# ZB2.net
KiCad netlist of a schematic drawn in Altium Designer
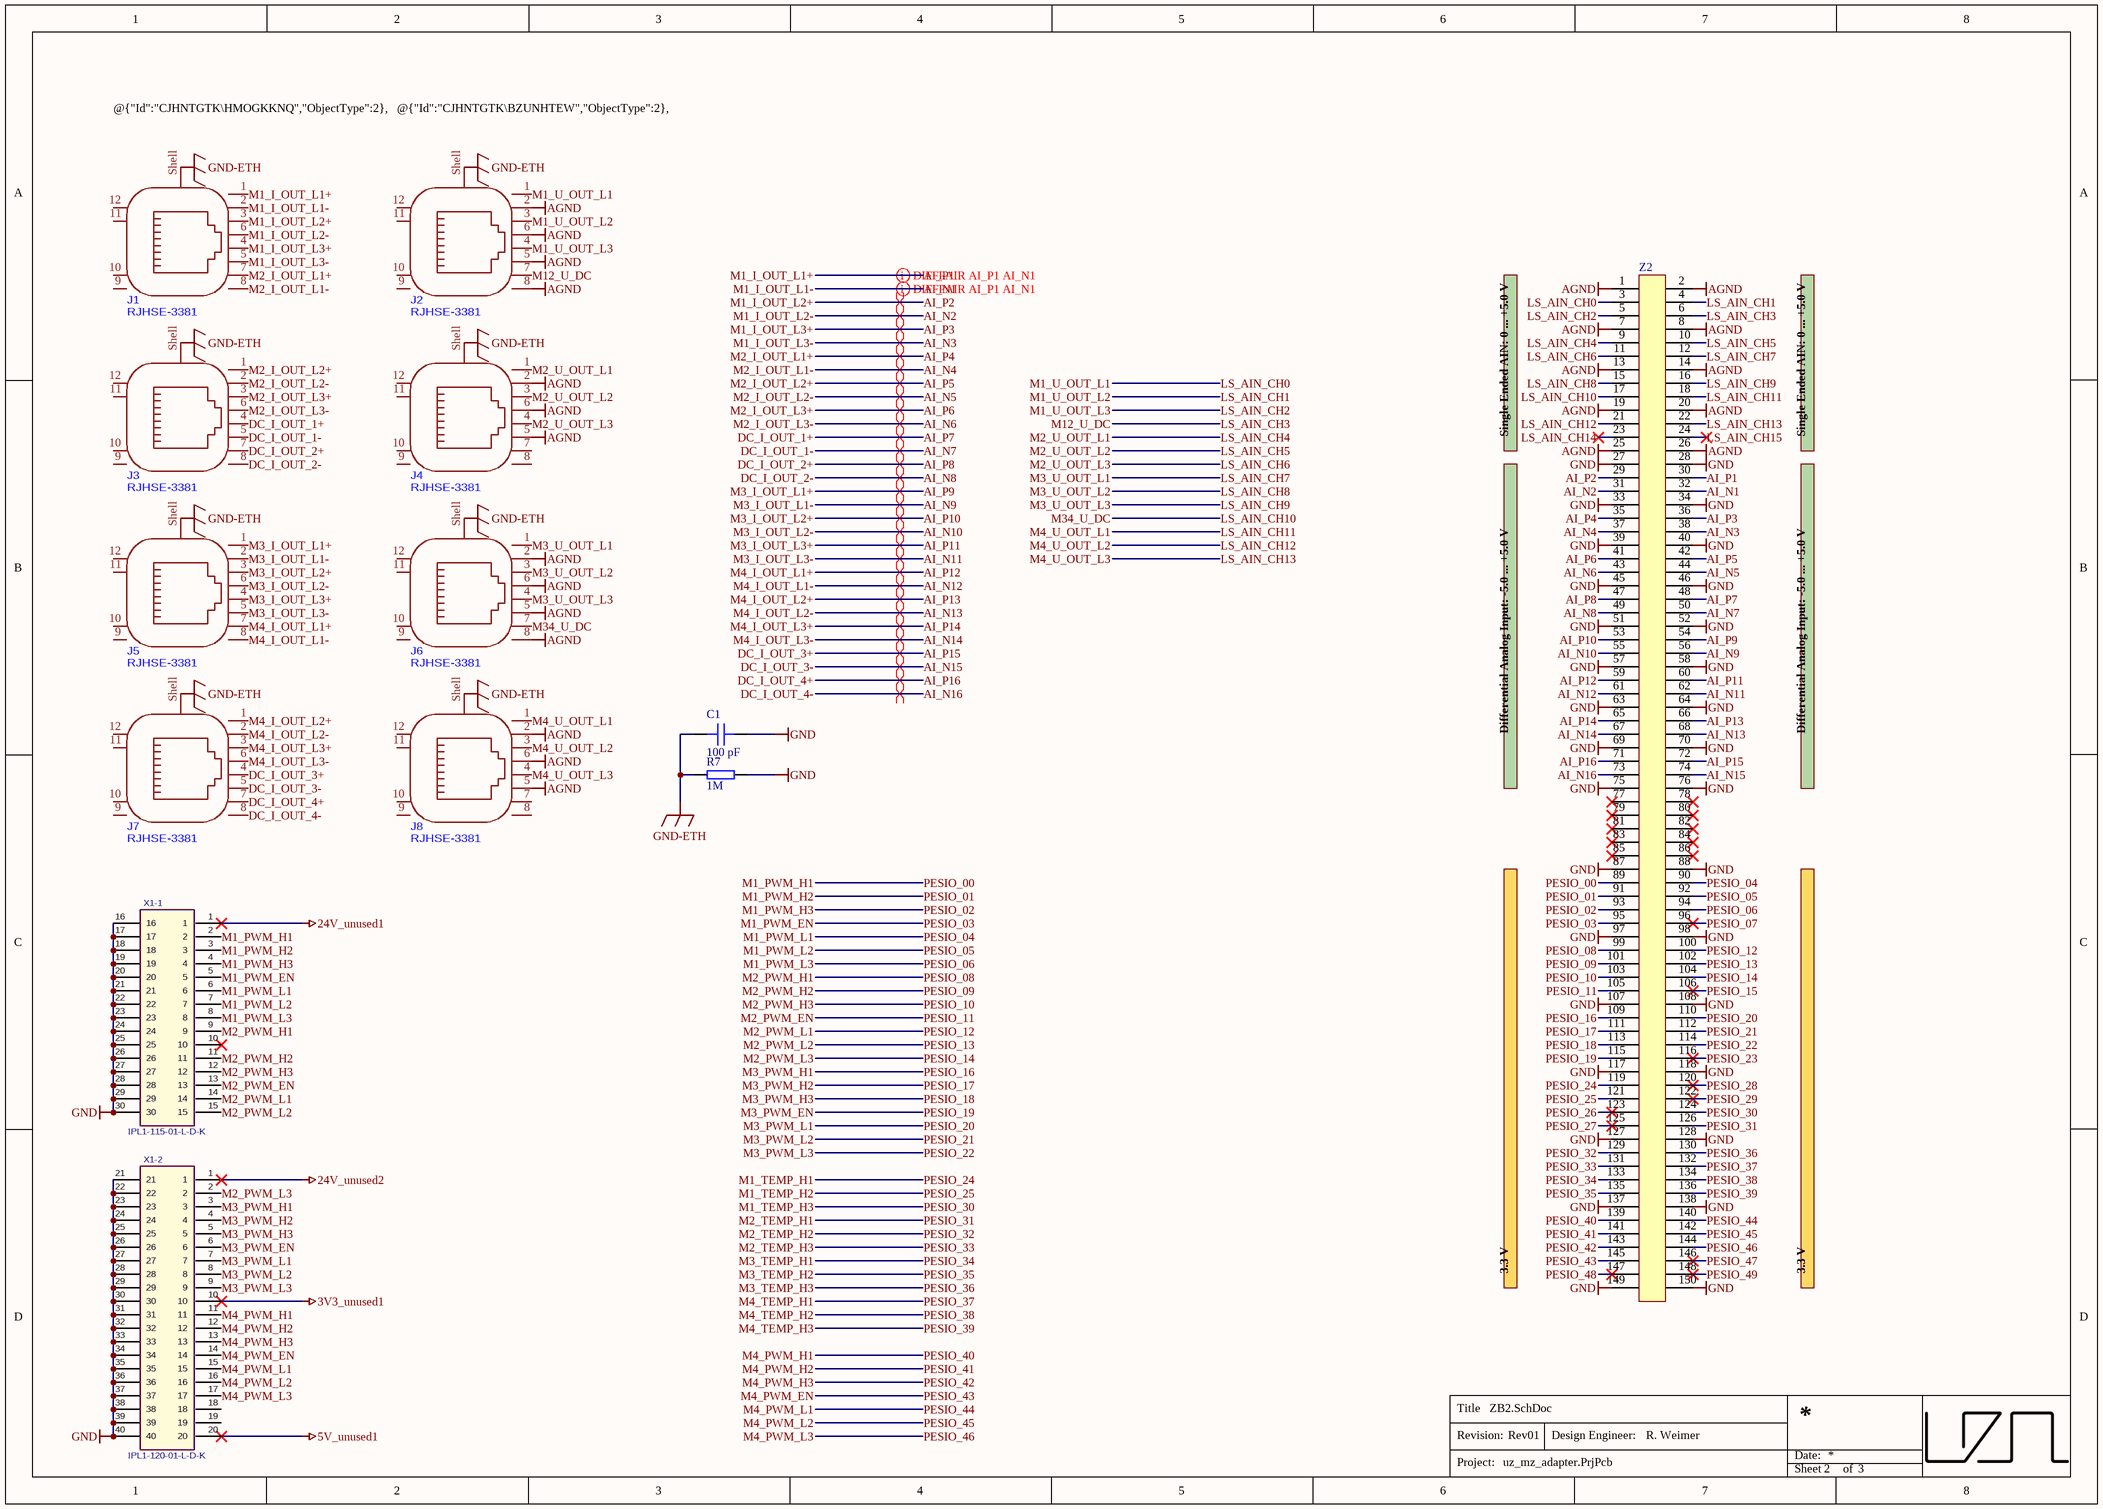
[diagram p0: ZB2.SchDoc]

(export (version "E")
  (design (tool "Eeschema 10.0.6"))
  (components
    (comp (ref "C1")
      (value "100 pF")
      (footprint "C_1206_TE")
      (description "2kV 100pF NP0 ±5% 1206 Multilayer Ceramic Capacitors MLCC - SMD/SMT ROHS")
      (fields
        (field (name "MANUFACTURER PART NUMBER") "CC1206JKNPODBN101")
        (field (name "MANUFACTURER") "YAGEO")
        (field (name "CREATED FROM") "AGeiger")
      )
      (libsource (lib "user") (part "Capacitor"))
    )
    (comp (ref "J1")
      (value "RJHSE-3381")
      (footprint "RJ45-TH_RJHSE-3381")
      (description "CAT5, RJ45 Connector, 1 port, vertical")
      (fields
        (field (name "MANUFACTURER") "Amphenol")
        (field (name "LCSC PART NUMBER") "C599439")
        (field (name "CREATED FROM") "RWeimer")
      )
      (libsource (lib "user") (part "RJHSE-3381"))
    )
    (comp (ref "J2")
      (value "RJHSE-3381")
      (footprint "RJ45-TH_RJHSE-3381")
      (description "CAT5, RJ45 Connector, 1 port, vertical")
      (fields
        (field (name "MANUFACTURER") "Amphenol")
        (field (name "LCSC PART NUMBER") "C599439")
        (field (name "CREATED FROM") "RWeimer")
      )
      (libsource (lib "user") (part "RJHSE-3381"))
    )
    (comp (ref "J3")
      (value "RJHSE-3381")
      (footprint "RJ45-TH_RJHSE-3381")
      (description "CAT5, RJ45 Connector, 1 port, vertical")
      (fields
        (field (name "MANUFACTURER") "Amphenol")
        (field (name "LCSC PART NUMBER") "C599439")
        (field (name "CREATED FROM") "RWeimer")
      )
      (libsource (lib "user") (part "RJHSE-3381"))
    )
    (comp (ref "J4")
      (value "RJHSE-3381")
      (footprint "RJ45-TH_RJHSE-3381")
      (description "CAT5, RJ45 Connector, 1 port, vertical")
      (fields
        (field (name "MANUFACTURER") "Amphenol")
        (field (name "LCSC PART NUMBER") "C599439")
        (field (name "CREATED FROM") "RWeimer")
      )
      (libsource (lib "user") (part "RJHSE-3381"))
    )
    (comp (ref "J5")
      (value "RJHSE-3381")
      (footprint "RJ45-TH_RJHSE-3381")
      (description "CAT5, RJ45 Connector, 1 port, vertical")
      (fields
        (field (name "MANUFACTURER") "Amphenol")
        (field (name "LCSC PART NUMBER") "C599439")
        (field (name "CREATED FROM") "RWeimer")
      )
      (libsource (lib "user") (part "RJHSE-3381"))
    )
    (comp (ref "J6")
      (value "RJHSE-3381")
      (footprint "RJ45-TH_RJHSE-3381")
      (description "CAT5, RJ45 Connector, 1 port, vertical")
      (fields
        (field (name "MANUFACTURER") "Amphenol")
        (field (name "LCSC PART NUMBER") "C599439")
        (field (name "CREATED FROM") "RWeimer")
      )
      (libsource (lib "user") (part "RJHSE-3381"))
    )
    (comp (ref "J7")
      (value "RJHSE-3381")
      (footprint "RJ45-TH_RJHSE-3381")
      (description "CAT5, RJ45 Connector, 1 port, vertical")
      (fields
        (field (name "MANUFACTURER") "Amphenol")
        (field (name "LCSC PART NUMBER") "C599439")
        (field (name "CREATED FROM") "RWeimer")
      )
      (libsource (lib "user") (part "RJHSE-3381"))
    )
    (comp (ref "J8")
      (value "RJHSE-3381")
      (footprint "RJ45-TH_RJHSE-3381")
      (description "CAT5, RJ45 Connector, 1 port, vertical")
      (fields
        (field (name "MANUFACTURER") "Amphenol")
        (field (name "LCSC PART NUMBER") "C599439")
        (field (name "CREATED FROM") "RWeimer")
      )
      (libsource (lib "user") (part "RJHSE-3381"))
    )
    (comp (ref "R7")
      (value "1M")
      (footprint "RES 1206_3216")
      (fields
        (field (name "MANUFACTURER PART NUMBER") "1206W4F1004T5E")
        (field (name "MANUFACTURER") "UNI-ROYAL")
        (field (name "TOLERANCE") "1%")
        (field (name "CREATED FROM") "AGeiger")
      )
      (libsource (lib "user") (part "Resistor"))
    )
    (comp (ref "X1-1")
      (value "IPL1-115-01-L-D-K")
      (footprint "IPL1-115-01-YYY-D-K")
      (description "2.54 mm Double Row Terminal Assembly")
      (fields
        (field (name "MANUFACTURER") "SAMTEC")
        (field (name "LCSC PART NUMBER") "C17431809")
        (field (name "CREATED FROM") "MGremer")
      )
      (libsource (lib "user") (part "IPL1-115-01-XX-D-XX"))
    )
    (comp (ref "X1-2")
      (value "IPL1-120-01-L-D-K")
      (footprint "SAMTEC_IPL1-120-01-X-D-K")
      (description "Terminal Assembly, Double Row, Thru-Hole, 2.54 mm x 2.54 mm Pitch, 40 Pins")
      (fields
        (field (name "MANUFACTURER") "SAMTEC")
        (field (name "LCSC PART NUMBER") "C17429670")
        (field (name "CREATED FROM") "PBaumann")
      )
      (libsource (lib "user") (part "IPL1-120-01-XX-D-XX"))
    )
    (comp (ref "Z2")
      (value "~")
      (footprint "ERM8-075-02.0-L-DV")
      (description "0.80 mm Edge Rate Rugged High Speed")
      (fields
        (field (name "MANUFACTURER PART NUMBER") "ERM8-075-02.0-L-DV-TR")
        (field (name "MANUFACTURER") "SAMTEC")
        (field (name "CREATED FROM") "AGeiger")
      )
      (libsource (lib "user") (part "CON-150"))
    )
  )
  (nets
    (net (code "1") (name "/AI_N1") (class "Default")
      (node (ref "J1") (pin "2") (pinfunction "2_2") (pintype "passive"))
      (node (ref "Z2") (pin "32") (pinfunction "32_32") (pintype "passive"))
    )
    (net (code "2") (name "/AI_N2") (class "Default")
      (node (ref "J1") (pin "6") (pinfunction "6_6") (pintype "passive"))
      (node (ref "Z2") (pin "31") (pinfunction "31_31") (pintype "passive"))
    )
    (net (code "3") (name "/AI_N3") (class "Default")
      (node (ref "J1") (pin "5") (pinfunction "5_5") (pintype "passive"))
      (node (ref "Z2") (pin "38") (pinfunction "38_38") (pintype "passive"))
    )
    (net (code "4") (name "/AI_N4") (class "Default")
      (node (ref "J1") (pin "8") (pinfunction "8_8") (pintype "passive"))
      (node (ref "Z2") (pin "37") (pinfunction "37_37") (pintype "passive"))
    )
    (net (code "5") (name "/AI_N5") (class "Default")
      (node (ref "J3") (pin "2") (pinfunction "2_2") (pintype "passive"))
      (node (ref "Z2") (pin "44") (pinfunction "44_44") (pintype "passive"))
    )
    (net (code "6") (name "/AI_N6") (class "Default")
      (node (ref "J3") (pin "6") (pinfunction "6_6") (pintype "passive"))
      (node (ref "Z2") (pin "43") (pinfunction "43_43") (pintype "passive"))
    )
    (net (code "7") (name "/AI_N7") (class "Default")
      (node (ref "J3") (pin "5") (pinfunction "5_5") (pintype "passive"))
      (node (ref "Z2") (pin "50") (pinfunction "50_50") (pintype "passive"))
    )
    (net (code "8") (name "/AI_N8") (class "Default")
      (node (ref "J3") (pin "8") (pinfunction "8_8") (pintype "passive"))
      (node (ref "Z2") (pin "49") (pinfunction "49_49") (pintype "passive"))
    )
    (net (code "9") (name "/AI_N9") (class "Default")
      (node (ref "J5") (pin "2") (pinfunction "2_2") (pintype "passive"))
      (node (ref "Z2") (pin "56") (pinfunction "56_56") (pintype "passive"))
    )
    (net (code "10") (name "/AI_N10") (class "Default")
      (node (ref "J5") (pin "6") (pinfunction "6_6") (pintype "passive"))
      (node (ref "Z2") (pin "55") (pinfunction "55_55") (pintype "passive"))
    )
    (net (code "11") (name "/AI_N11") (class "Default")
      (node (ref "J5") (pin "5") (pinfunction "5_5") (pintype "passive"))
      (node (ref "Z2") (pin "62") (pinfunction "62_62") (pintype "passive"))
    )
    (net (code "12") (name "/AI_N12") (class "Default")
      (node (ref "J5") (pin "8") (pinfunction "8_8") (pintype "passive"))
      (node (ref "Z2") (pin "61") (pinfunction "61_61") (pintype "passive"))
    )
    (net (code "13") (name "/AI_N13") (class "Default")
      (node (ref "J7") (pin "2") (pinfunction "2_2") (pintype "passive"))
      (node (ref "Z2") (pin "68") (pinfunction "68_68") (pintype "passive"))
    )
    (net (code "14") (name "/AI_N14") (class "Default")
      (node (ref "J7") (pin "6") (pinfunction "6_6") (pintype "passive"))
      (node (ref "Z2") (pin "67") (pinfunction "67_67") (pintype "passive"))
    )
    (net (code "15") (name "/AI_N15") (class "Default")
      (node (ref "J7") (pin "5") (pinfunction "5_5") (pintype "passive"))
      (node (ref "Z2") (pin "74") (pinfunction "74_74") (pintype "passive"))
    )
    (net (code "16") (name "/AI_N16") (class "Default")
      (node (ref "J7") (pin "8") (pinfunction "8_8") (pintype "passive"))
      (node (ref "Z2") (pin "73") (pinfunction "73_73") (pintype "passive"))
    )
    (net (code "17") (name "/AI_P1") (class "Default")
      (node (ref "J1") (pin "1") (pinfunction "1_1") (pintype "passive"))
      (node (ref "Z2") (pin "30") (pinfunction "30_30") (pintype "passive"))
    )
    (net (code "18") (name "/AI_P2") (class "Default")
      (node (ref "J1") (pin "3") (pinfunction "3_3") (pintype "passive"))
      (node (ref "Z2") (pin "29") (pinfunction "29_29") (pintype "passive"))
    )
    (net (code "19") (name "/AI_P3") (class "Default")
      (node (ref "J1") (pin "4") (pinfunction "5_4") (pintype "passive"))
      (node (ref "Z2") (pin "36") (pinfunction "36_36") (pintype "passive"))
    )
    (net (code "20") (name "/AI_P4") (class "Default")
      (node (ref "J1") (pin "7") (pinfunction "7_7") (pintype "passive"))
      (node (ref "Z2") (pin "35") (pinfunction "35_35") (pintype "passive"))
    )
    (net (code "21") (name "/AI_P5") (class "Default")
      (node (ref "J3") (pin "1") (pinfunction "1_1") (pintype "passive"))
      (node (ref "Z2") (pin "42") (pinfunction "42_42") (pintype "passive"))
    )
    (net (code "22") (name "/AI_P6") (class "Default")
      (node (ref "J3") (pin "3") (pinfunction "3_3") (pintype "passive"))
      (node (ref "Z2") (pin "41") (pinfunction "41_41") (pintype "passive"))
    )
    (net (code "23") (name "/AI_P7") (class "Default")
      (node (ref "J3") (pin "4") (pinfunction "5_4") (pintype "passive"))
      (node (ref "Z2") (pin "48") (pinfunction "48_48") (pintype "passive"))
    )
    (net (code "24") (name "/AI_P8") (class "Default")
      (node (ref "J3") (pin "7") (pinfunction "7_7") (pintype "passive"))
      (node (ref "Z2") (pin "47") (pinfunction "47_47") (pintype "passive"))
    )
    (net (code "25") (name "/AI_P9") (class "Default")
      (node (ref "J5") (pin "1") (pinfunction "1_1") (pintype "passive"))
      (node (ref "Z2") (pin "54") (pinfunction "54_54") (pintype "passive"))
    )
    (net (code "26") (name "/AI_P10") (class "Default")
      (node (ref "J5") (pin "3") (pinfunction "3_3") (pintype "passive"))
      (node (ref "Z2") (pin "53") (pinfunction "53_53") (pintype "passive"))
    )
    (net (code "27") (name "/AI_P11") (class "Default")
      (node (ref "J5") (pin "4") (pinfunction "5_4") (pintype "passive"))
      (node (ref "Z2") (pin "60") (pinfunction "60_60") (pintype "passive"))
    )
    (net (code "28") (name "/AI_P12") (class "Default")
      (node (ref "J5") (pin "7") (pinfunction "7_7") (pintype "passive"))
      (node (ref "Z2") (pin "59") (pinfunction "59_59") (pintype "passive"))
    )
    (net (code "29") (name "/AI_P13") (class "Default")
      (node (ref "J7") (pin "1") (pinfunction "1_1") (pintype "passive"))
      (node (ref "Z2") (pin "66") (pinfunction "66_66") (pintype "passive"))
    )
    (net (code "30") (name "/AI_P14") (class "Default")
      (node (ref "J7") (pin "3") (pinfunction "3_3") (pintype "passive"))
      (node (ref "Z2") (pin "65") (pinfunction "65_65") (pintype "passive"))
    )
    (net (code "31") (name "/AI_P15") (class "Default")
      (node (ref "J7") (pin "4") (pinfunction "5_4") (pintype "passive"))
      (node (ref "Z2") (pin "72") (pinfunction "72_72") (pintype "passive"))
    )
    (net (code "32") (name "/AI_P16") (class "Default")
      (node (ref "J7") (pin "7") (pinfunction "7_7") (pintype "passive"))
      (node (ref "Z2") (pin "71") (pinfunction "71_71") (pintype "passive"))
    )
    (net (code "33") (name "/LS_AIN_CH0") (class "Default")
      (node (ref "J2") (pin "1") (pinfunction "1_1") (pintype "passive"))
      (node (ref "Z2") (pin "3") (pinfunction "3_3") (pintype "passive"))
    )
    (net (code "34") (name "/LS_AIN_CH1") (class "Default")
      (node (ref "J2") (pin "3") (pinfunction "3_3") (pintype "passive"))
      (node (ref "Z2") (pin "4") (pinfunction "4_4") (pintype "passive"))
    )
    (net (code "35") (name "/LS_AIN_CH2") (class "Default")
      (node (ref "J2") (pin "4") (pinfunction "5_4") (pintype "passive"))
      (node (ref "Z2") (pin "5") (pinfunction "5_5") (pintype "passive"))
    )
    (net (code "36") (name "/LS_AIN_CH3") (class "Default")
      (node (ref "J2") (pin "7") (pinfunction "7_7") (pintype "passive"))
      (node (ref "Z2") (pin "6") (pinfunction "6_6") (pintype "passive"))
    )
    (net (code "37") (name "/LS_AIN_CH4") (class "Default")
      (node (ref "J4") (pin "1") (pinfunction "1_1") (pintype "passive"))
      (node (ref "Z2") (pin "9") (pinfunction "9_9") (pintype "passive"))
    )
    (net (code "38") (name "/LS_AIN_CH5") (class "Default")
      (node (ref "J4") (pin "3") (pinfunction "3_3") (pintype "passive"))
      (node (ref "Z2") (pin "10") (pinfunction "10_10") (pintype "passive"))
    )
    (net (code "39") (name "/LS_AIN_CH6") (class "Default")
      (node (ref "J4") (pin "4") (pinfunction "5_4") (pintype "passive"))
      (node (ref "Z2") (pin "11") (pinfunction "11_11") (pintype "passive"))
    )
    (net (code "40") (name "/LS_AIN_CH7") (class "Default")
      (node (ref "J6") (pin "1") (pinfunction "1_1") (pintype "passive"))
      (node (ref "Z2") (pin "12") (pinfunction "12_12") (pintype "passive"))
    )
    (net (code "41") (name "/LS_AIN_CH8") (class "Default")
      (node (ref "J6") (pin "3") (pinfunction "3_3") (pintype "passive"))
      (node (ref "Z2") (pin "15") (pinfunction "15_15") (pintype "passive"))
    )
    (net (code "42") (name "/LS_AIN_CH9") (class "Default")
      (node (ref "J6") (pin "4") (pinfunction "5_4") (pintype "passive"))
      (node (ref "Z2") (pin "16") (pinfunction "16_16") (pintype "passive"))
    )
    (net (code "43") (name "/LS_AIN_CH10") (class "Default")
      (node (ref "J6") (pin "7") (pinfunction "7_7") (pintype "passive"))
      (node (ref "Z2") (pin "17") (pinfunction "17_17") (pintype "passive"))
    )
    (net (code "44") (name "/LS_AIN_CH11") (class "Default")
      (node (ref "J8") (pin "1") (pinfunction "1_1") (pintype "passive"))
      (node (ref "Z2") (pin "18") (pinfunction "18_18") (pintype "passive"))
    )
    (net (code "45") (name "/LS_AIN_CH12") (class "Default")
      (node (ref "J8") (pin "3") (pinfunction "3_3") (pintype "passive"))
      (node (ref "Z2") (pin "21") (pinfunction "21_21") (pintype "passive"))
    )
    (net (code "46") (name "/LS_AIN_CH13") (class "Default")
      (node (ref "J8") (pin "4") (pinfunction "5_4") (pintype "passive"))
      (node (ref "Z2") (pin "22") (pinfunction "22_22") (pintype "passive"))
    )
    (net (code "47") (name "/LS_AIN_CH14") (class "Default")
      (node (ref "Z2") (pin "23") (pinfunction "23_23") (pintype "passive+no_connect"))
    )
    (net (code "48") (name "/LS_AIN_CH15") (class "Default")
      (node (ref "Z2") (pin "24") (pinfunction "24_24") (pintype "passive+no_connect"))
    )
    (net (code "49") (name "/M1_PWM_EN") (class "Default")
      (node (ref "X1-1") (pin "5") (pinfunction "5_5") (pintype "passive"))
      (node (ref "Z2") (pin "95") (pinfunction "95_95") (pintype "passive"))
    )
    (net (code "50") (name "/M1_PWM_H1") (class "Default")
      (node (ref "X1-1") (pin "2") (pinfunction "2_2") (pintype "passive"))
      (node (ref "Z2") (pin "89") (pinfunction "89_89") (pintype "passive"))
    )
    (net (code "51") (name "/M1_PWM_H2") (class "Default")
      (node (ref "X1-1") (pin "3") (pinfunction "3_3") (pintype "passive"))
      (node (ref "Z2") (pin "91") (pinfunction "91_91") (pintype "passive"))
    )
    (net (code "52") (name "/M1_PWM_H3") (class "Default")
      (node (ref "X1-1") (pin "4") (pinfunction "4_4") (pintype "passive"))
      (node (ref "Z2") (pin "93") (pinfunction "93_93") (pintype "passive"))
    )
    (net (code "53") (name "/M1_PWM_L1") (class "Default")
      (node (ref "X1-1") (pin "6") (pinfunction "6_6") (pintype "passive"))
      (node (ref "Z2") (pin "90") (pinfunction "90_90") (pintype "passive"))
    )
    (net (code "54") (name "/M1_PWM_L2") (class "Default")
      (node (ref "X1-1") (pin "7") (pinfunction "7_7") (pintype "passive"))
      (node (ref "Z2") (pin "92") (pinfunction "92_92") (pintype "passive"))
    )
    (net (code "55") (name "/M1_PWM_L3") (class "Default")
      (node (ref "X1-1") (pin "8") (pinfunction "8_8") (pintype "passive"))
      (node (ref "Z2") (pin "94") (pinfunction "94_94") (pintype "passive"))
    )
    (net (code "56") (name "/M1_TEMP_H1") (class "Default")
      (node (ref "Z2") (pin "119") (pinfunction "119_119") (pintype "passive"))
    )
    (net (code "57") (name "/M1_TEMP_H2") (class "Default")
      (node (ref "Z2") (pin "121") (pinfunction "121_121") (pintype "passive"))
    )
    (net (code "58") (name "/M1_TEMP_H3") (class "Default")
      (node (ref "Z2") (pin "124") (pinfunction "124_124") (pintype "passive"))
    )
    (net (code "59") (name "/M2_PWM_EN") (class "Default")
      (node (ref "X1-1") (pin "13") (pinfunction "13_13") (pintype "passive"))
      (node (ref "Z2") (pin "105") (pinfunction "105_105") (pintype "passive"))
    )
    (net (code "60") (name "/M2_PWM_H1") (class "Default")
      (node (ref "X1-1") (pin "9") (pinfunction "9_9") (pintype "passive"))
      (node (ref "Z2") (pin "99") (pinfunction "99_99") (pintype "passive"))
    )
    (net (code "61") (name "/M2_PWM_H2") (class "Default")
      (node (ref "X1-1") (pin "11") (pinfunction "11_11") (pintype "passive"))
      (node (ref "Z2") (pin "101") (pinfunction "101_101") (pintype "passive"))
    )
    (net (code "62") (name "/M2_PWM_H3") (class "Default")
      (node (ref "X1-1") (pin "12") (pinfunction "12_12") (pintype "passive"))
      (node (ref "Z2") (pin "103") (pinfunction "103_103") (pintype "passive"))
    )
    (net (code "63") (name "/M2_PWM_L1") (class "Default")
      (node (ref "X1-1") (pin "14") (pinfunction "14_14") (pintype "passive"))
      (node (ref "Z2") (pin "100") (pinfunction "100_100") (pintype "passive"))
    )
    (net (code "64") (name "/M2_PWM_L2") (class "Default")
      (node (ref "X1-1") (pin "15") (pinfunction "15_15") (pintype "passive"))
      (node (ref "Z2") (pin "102") (pinfunction "102_102") (pintype "passive"))
    )
    (net (code "65") (name "/M2_PWM_L3") (class "Default")
      (node (ref "X1-2") (pin "2") (pinfunction "2_2") (pintype "passive"))
      (node (ref "Z2") (pin "104") (pinfunction "104_104") (pintype "passive"))
    )
    (net (code "66") (name "/M2_TEMP_H1") (class "Default")
      (node (ref "Z2") (pin "126") (pinfunction "126_126") (pintype "passive"))
    )
    (net (code "67") (name "/M2_TEMP_H2") (class "Default")
      (node (ref "Z2") (pin "129") (pinfunction "129_129") (pintype "passive"))
    )
    (net (code "68") (name "/M2_TEMP_H3") (class "Default")
      (node (ref "Z2") (pin "131") (pinfunction "131_131") (pintype "passive"))
    )
    (net (code "69") (name "/M3_PWM_EN") (class "Default")
      (node (ref "X1-2") (pin "6") (pinfunction "6_6") (pintype "passive"))
      (node (ref "Z2") (pin "115") (pinfunction "115_115") (pintype "passive"))
    )
    (net (code "70") (name "/M3_PWM_H1") (class "Default")
      (node (ref "X1-2") (pin "3") (pinfunction "3_3") (pintype "passive"))
      (node (ref "Z2") (pin "109") (pinfunction "109_109") (pintype "passive"))
    )
    (net (code "71") (name "/M3_PWM_H2") (class "Default")
      (node (ref "X1-2") (pin "4") (pinfunction "4_4") (pintype "passive"))
      (node (ref "Z2") (pin "111") (pinfunction "111_111") (pintype "passive"))
    )
    (net (code "72") (name "/M3_PWM_H3") (class "Default")
      (node (ref "X1-2") (pin "5") (pinfunction "5_5") (pintype "passive"))
      (node (ref "Z2") (pin "113") (pinfunction "113_113") (pintype "passive"))
    )
    (net (code "73") (name "/M3_PWM_L1") (class "Default")
      (node (ref "X1-2") (pin "7") (pinfunction "7_7") (pintype "passive"))
      (node (ref "Z2") (pin "110") (pinfunction "110_110") (pintype "passive"))
    )
    (net (code "74") (name "/M3_PWM_L2") (class "Default")
      (node (ref "X1-2") (pin "8") (pinfunction "8_8") (pintype "passive"))
      (node (ref "Z2") (pin "112") (pinfunction "112_112") (pintype "passive"))
    )
    (net (code "75") (name "/M3_PWM_L3") (class "Default")
      (node (ref "X1-2") (pin "9") (pinfunction "9_9") (pintype "passive"))
      (node (ref "Z2") (pin "114") (pinfunction "114_114") (pintype "passive"))
    )
    (net (code "76") (name "/M3_TEMP_H1") (class "Default")
      (node (ref "Z2") (pin "133") (pinfunction "133_133") (pintype "passive"))
    )
    (net (code "77") (name "/M3_TEMP_H2") (class "Default")
      (node (ref "Z2") (pin "135") (pinfunction "135_135") (pintype "passive"))
    )
    (net (code "78") (name "/M3_TEMP_H3") (class "Default")
      (node (ref "Z2") (pin "130") (pinfunction "130_130") (pintype "passive"))
    )
    (net (code "79") (name "/M4_PWM_EN") (class "Default")
      (node (ref "X1-2") (pin "14") (pinfunction "14_14") (pintype "passive"))
      (node (ref "Z2") (pin "145") (pinfunction "145_145") (pintype "passive"))
    )
    (net (code "80") (name "/M4_PWM_H1") (class "Default")
      (node (ref "X1-2") (pin "11") (pinfunction "11_11") (pintype "passive"))
      (node (ref "Z2") (pin "139") (pinfunction "139_139") (pintype "passive"))
    )
    (net (code "81") (name "/M4_PWM_H2") (class "Default")
      (node (ref "X1-2") (pin "12") (pinfunction "12_12") (pintype "passive"))
      (node (ref "Z2") (pin "141") (pinfunction "141_141") (pintype "passive"))
    )
    (net (code "82") (name "/M4_PWM_H3") (class "Default")
      (node (ref "X1-2") (pin "13") (pinfunction "13_13") (pintype "passive"))
      (node (ref "Z2") (pin "143") (pinfunction "143_143") (pintype "passive"))
    )
    (net (code "83") (name "/M4_PWM_L1") (class "Default")
      (node (ref "X1-2") (pin "15") (pinfunction "15_15") (pintype "passive"))
      (node (ref "Z2") (pin "140") (pinfunction "140_140") (pintype "passive"))
    )
    (net (code "84") (name "/M4_PWM_L2") (class "Default")
      (node (ref "X1-2") (pin "16") (pinfunction "16_16") (pintype "passive"))
      (node (ref "Z2") (pin "142") (pinfunction "142_142") (pintype "passive"))
    )
    (net (code "85") (name "/M4_PWM_L3") (class "Default")
      (node (ref "X1-2") (pin "17") (pinfunction "17_17") (pintype "passive"))
      (node (ref "Z2") (pin "144") (pinfunction "144_144") (pintype "passive"))
    )
    (net (code "86") (name "/M4_TEMP_H1") (class "Default")
      (node (ref "Z2") (pin "132") (pinfunction "132_132") (pintype "passive"))
    )
    (net (code "87") (name "/M4_TEMP_H2") (class "Default")
      (node (ref "Z2") (pin "134") (pinfunction "134_134") (pintype "passive"))
    )
    (net (code "88") (name "/M4_TEMP_H3") (class "Default")
      (node (ref "Z2") (pin "136") (pinfunction "136_136") (pintype "passive"))
    )
    (net (code "89") (name "/PESIO_07") (class "Default")
      (node (ref "Z2") (pin "96") (pinfunction "96_96") (pintype "passive+no_connect"))
    )
    (net (code "90") (name "/PESIO_15") (class "Default")
      (node (ref "Z2") (pin "106") (pinfunction "106_106") (pintype "passive+no_connect"))
    )
    (net (code "91") (name "/PESIO_23") (class "Default")
      (node (ref "Z2") (pin "116") (pinfunction "116_116") (pintype "passive+no_connect"))
    )
    (net (code "92") (name "/PESIO_26") (class "Default")
      (node (ref "Z2") (pin "123") (pinfunction "123_123") (pintype "passive+no_connect"))
    )
    (net (code "93") (name "/PESIO_27") (class "Default")
      (node (ref "Z2") (pin "125") (pinfunction "125_125") (pintype "passive+no_connect"))
    )
    (net (code "94") (name "/PESIO_28") (class "Default")
      (node (ref "Z2") (pin "120") (pinfunction "120_120") (pintype "passive+no_connect"))
    )
    (net (code "95") (name "/PESIO_29") (class "Default")
      (node (ref "Z2") (pin "122") (pinfunction "122_122") (pintype "passive+no_connect"))
    )
    (net (code "96") (name "/PESIO_47") (class "Default")
      (node (ref "Z2") (pin "146") (pinfunction "146_146") (pintype "passive+no_connect"))
    )
    (net (code "97") (name "/PESIO_48") (class "Default")
      (node (ref "Z2") (pin "147") (pinfunction "147_147") (pintype "passive+no_connect"))
    )
    (net (code "98") (name "/PESIO_49") (class "Default")
      (node (ref "Z2") (pin "148") (pinfunction "148_148") (pintype "passive+no_connect"))
    )
    (net (code "99") (name "3V3_unused1") (class "Default")
      (node (ref "X1-2") (pin "10") (pinfunction "10_10") (pintype "passive"))
    )
    (net (code "100") (name "5V_unused1") (class "Default")
      (node (ref "X1-2") (pin "20") (pinfunction "20_20") (pintype "passive"))
    )
    (net (code "101") (name "24V_unused1") (class "Default")
      (node (ref "X1-1") (pin "1") (pinfunction "1_1") (pintype "passive"))
    )
    (net (code "102") (name "24V_unused2") (class "Default")
      (node (ref "X1-2") (pin "1") (pinfunction "1_1") (pintype "passive"))
    )
    (net (code "103") (name "AGND") (class "Default")
      (node (ref "J2") (pin "2") (pinfunction "2_2") (pintype "passive"))
      (node (ref "J2") (pin "5") (pinfunction "5_5") (pintype "passive"))
      (node (ref "J2") (pin "6") (pinfunction "6_6") (pintype "passive"))
      (node (ref "J2") (pin "8") (pinfunction "8_8") (pintype "passive"))
      (node (ref "J4") (pin "2") (pinfunction "2_2") (pintype "passive"))
      (node (ref "J4") (pin "5") (pinfunction "5_5") (pintype "passive"))
      (node (ref "J4") (pin "6") (pinfunction "6_6") (pintype "passive"))
      (node (ref "J6") (pin "2") (pinfunction "2_2") (pintype "passive"))
      (node (ref "J6") (pin "5") (pinfunction "5_5") (pintype "passive"))
      (node (ref "J6") (pin "6") (pinfunction "6_6") (pintype "passive"))
      (node (ref "J6") (pin "8") (pinfunction "8_8") (pintype "passive"))
      (node (ref "J8") (pin "2") (pinfunction "2_2") (pintype "passive"))
      (node (ref "J8") (pin "5") (pinfunction "5_5") (pintype "passive"))
      (node (ref "J8") (pin "6") (pinfunction "6_6") (pintype "passive"))
      (node (ref "Z2") (pin "1") (pinfunction "1_1") (pintype "passive"))
      (node (ref "Z2") (pin "13") (pinfunction "13_13") (pintype "passive"))
      (node (ref "Z2") (pin "14") (pinfunction "14_14") (pintype "passive"))
      (node (ref "Z2") (pin "19") (pinfunction "19_19") (pintype "passive"))
      (node (ref "Z2") (pin "2") (pinfunction "2_2") (pintype "passive"))
      (node (ref "Z2") (pin "20") (pinfunction "20_20") (pintype "passive"))
      (node (ref "Z2") (pin "25") (pinfunction "25_25") (pintype "passive"))
      (node (ref "Z2") (pin "26") (pinfunction "26_26") (pintype "passive"))
      (node (ref "Z2") (pin "7") (pinfunction "7_7") (pintype "passive"))
      (node (ref "Z2") (pin "8") (pinfunction "8_8") (pintype "passive"))
    )
    (net (code "104") (name "GND") (class "Default")
      (node (ref "C1") (pin "2") (pinfunction "2_2") (pintype "passive"))
      (node (ref "R7") (pin "2") (pinfunction "2_2") (pintype "passive"))
      (node (ref "X1-1") (pin "16") (pinfunction "16_16") (pintype "passive"))
      (node (ref "X1-1") (pin "17") (pinfunction "17_17") (pintype "passive"))
      (node (ref "X1-1") (pin "18") (pinfunction "18_18") (pintype "passive"))
      (node (ref "X1-1") (pin "19") (pinfunction "19_19") (pintype "passive"))
      (node (ref "X1-1") (pin "20") (pinfunction "20_20") (pintype "passive"))
      (node (ref "X1-1") (pin "21") (pinfunction "21_21") (pintype "passive"))
      (node (ref "X1-1") (pin "22") (pinfunction "22_22") (pintype "passive"))
      (node (ref "X1-1") (pin "23") (pinfunction "23_23") (pintype "passive"))
      (node (ref "X1-1") (pin "24") (pinfunction "24_24") (pintype "passive"))
      (node (ref "X1-1") (pin "25") (pinfunction "25_25") (pintype "passive"))
      (node (ref "X1-1") (pin "26") (pinfunction "26_26") (pintype "passive"))
      (node (ref "X1-1") (pin "27") (pinfunction "27_27") (pintype "passive"))
      (node (ref "X1-1") (pin "28") (pinfunction "28_28") (pintype "passive"))
      (node (ref "X1-1") (pin "29") (pinfunction "29_29") (pintype "passive"))
      (node (ref "X1-1") (pin "30") (pinfunction "30_30") (pintype "passive"))
      (node (ref "X1-2") (pin "21") (pinfunction "21_21") (pintype "passive"))
      (node (ref "X1-2") (pin "22") (pinfunction "22_22") (pintype "passive"))
      (node (ref "X1-2") (pin "23") (pinfunction "23_23") (pintype "passive"))
      (node (ref "X1-2") (pin "24") (pinfunction "24_24") (pintype "passive"))
      (node (ref "X1-2") (pin "25") (pinfunction "25_25") (pintype "passive"))
      (node (ref "X1-2") (pin "26") (pinfunction "26_26") (pintype "passive"))
      (node (ref "X1-2") (pin "27") (pinfunction "27_27") (pintype "passive"))
      (node (ref "X1-2") (pin "28") (pinfunction "28_28") (pintype "passive"))
      (node (ref "X1-2") (pin "29") (pinfunction "29_29") (pintype "passive"))
      (node (ref "X1-2") (pin "30") (pinfunction "30_30") (pintype "passive"))
      (node (ref "X1-2") (pin "31") (pinfunction "31_31") (pintype "passive"))
      (node (ref "X1-2") (pin "32") (pinfunction "32_32") (pintype "passive"))
      (node (ref "X1-2") (pin "33") (pinfunction "33_33") (pintype "passive"))
      (node (ref "X1-2") (pin "34") (pinfunction "34_34") (pintype "passive"))
      (node (ref "X1-2") (pin "35") (pinfunction "35_35") (pintype "passive"))
      (node (ref "X1-2") (pin "36") (pinfunction "36_36") (pintype "passive"))
      (node (ref "X1-2") (pin "37") (pinfunction "37_37") (pintype "passive"))
      (node (ref "X1-2") (pin "38") (pinfunction "38_38") (pintype "passive"))
      (node (ref "X1-2") (pin "39") (pinfunction "39_39") (pintype "passive"))
      (node (ref "X1-2") (pin "40") (pinfunction "40_40") (pintype "passive"))
      (node (ref "Z2") (pin "107") (pinfunction "107_107") (pintype "passive"))
      (node (ref "Z2") (pin "108") (pinfunction "108_108") (pintype "passive"))
      (node (ref "Z2") (pin "117") (pinfunction "117_117") (pintype "passive"))
      (node (ref "Z2") (pin "118") (pinfunction "118_118") (pintype "passive"))
      (node (ref "Z2") (pin "127") (pinfunction "127_127") (pintype "passive"))
      (node (ref "Z2") (pin "128") (pinfunction "128_128") (pintype "passive"))
      (node (ref "Z2") (pin "137") (pinfunction "137_137") (pintype "passive"))
      (node (ref "Z2") (pin "138") (pinfunction "138_138") (pintype "passive"))
      (node (ref "Z2") (pin "149") (pinfunction "149_149") (pintype "passive"))
      (node (ref "Z2") (pin "150") (pinfunction "150_150") (pintype "passive"))
      (node (ref "Z2") (pin "27") (pinfunction "27_27") (pintype "passive"))
      (node (ref "Z2") (pin "28") (pinfunction "28_28") (pintype "passive"))
      (node (ref "Z2") (pin "33") (pinfunction "33_33") (pintype "passive"))
      (node (ref "Z2") (pin "34") (pinfunction "34_34") (pintype "passive"))
      (node (ref "Z2") (pin "39") (pinfunction "39_39") (pintype "passive"))
      (node (ref "Z2") (pin "40") (pinfunction "40_40") (pintype "passive"))
      (node (ref "Z2") (pin "45") (pinfunction "45_45") (pintype "passive"))
      (node (ref "Z2") (pin "46") (pinfunction "46_46") (pintype "passive"))
      (node (ref "Z2") (pin "51") (pinfunction "51_51") (pintype "passive"))
      (node (ref "Z2") (pin "52") (pinfunction "52_52") (pintype "passive"))
      (node (ref "Z2") (pin "57") (pinfunction "57_57") (pintype "passive"))
      (node (ref "Z2") (pin "58") (pinfunction "58_58") (pintype "passive"))
      (node (ref "Z2") (pin "63") (pinfunction "63_63") (pintype "passive"))
      (node (ref "Z2") (pin "64") (pinfunction "64_64") (pintype "passive"))
      (node (ref "Z2") (pin "69") (pinfunction "69_69") (pintype "passive"))
      (node (ref "Z2") (pin "70") (pinfunction "70_70") (pintype "passive"))
      (node (ref "Z2") (pin "75") (pinfunction "75_75") (pintype "passive"))
      (node (ref "Z2") (pin "76") (pinfunction "76_76") (pintype "passive"))
      (node (ref "Z2") (pin "87") (pinfunction "87_87") (pintype "passive"))
      (node (ref "Z2") (pin "88") (pinfunction "88_88") (pintype "passive"))
      (node (ref "Z2") (pin "97") (pinfunction "97_97") (pintype "passive"))
      (node (ref "Z2") (pin "98") (pinfunction "98_98") (pintype "passive"))
    )
    (net (code "105") (name "GND-ETH") (class "Default")
      (node (ref "C1") (pin "1") (pinfunction "1_1") (pintype "passive"))
      (node (ref "J1") (pin "Shell") (pinfunction "Shell_Shell") (pintype "passive"))
      (node (ref "J2") (pin "Shell") (pinfunction "Shell_Shell") (pintype "passive"))
      (node (ref "J3") (pin "Shell") (pinfunction "Shell_Shell") (pintype "passive"))
      (node (ref "J4") (pin "Shell") (pinfunction "Shell_Shell") (pintype "passive"))
      (node (ref "J5") (pin "Shell") (pinfunction "Shell_Shell") (pintype "passive"))
      (node (ref "J6") (pin "Shell") (pinfunction "Shell_Shell") (pintype "passive"))
      (node (ref "J7") (pin "Shell") (pinfunction "Shell_Shell") (pintype "passive"))
      (node (ref "J8") (pin "Shell") (pinfunction "Shell_Shell") (pintype "passive"))
      (node (ref "R7") (pin "1") (pinfunction "1_1") (pintype "passive"))
    )
    (net (code "106") (name "unconnected-(J1-Pad9)") (class "Default")
      (node (ref "J1") (pin "9") (pinfunction "9_9") (pintype "passive"))
    )
    (net (code "107") (name "unconnected-(J1-Pad10)") (class "Default")
      (node (ref "J1") (pin "10") (pinfunction "10_10") (pintype "passive"))
    )
    (net (code "108") (name "unconnected-(J1-Pad11)") (class "Default")
      (node (ref "J1") (pin "11") (pinfunction "11_11") (pintype "passive"))
    )
    (net (code "109") (name "unconnected-(J1-Pad12)") (class "Default")
      (node (ref "J1") (pin "12") (pinfunction "12_12") (pintype "passive"))
    )
    (net (code "110") (name "unconnected-(J2-Pad9)") (class "Default")
      (node (ref "J2") (pin "9") (pinfunction "9_9") (pintype "passive"))
    )
    (net (code "111") (name "unconnected-(J2-Pad10)") (class "Default")
      (node (ref "J2") (pin "10") (pinfunction "10_10") (pintype "passive"))
    )
    (net (code "112") (name "unconnected-(J2-Pad11)") (class "Default")
      (node (ref "J2") (pin "11") (pinfunction "11_11") (pintype "passive"))
    )
    (net (code "113") (name "unconnected-(J2-Pad12)") (class "Default")
      (node (ref "J2") (pin "12") (pinfunction "12_12") (pintype "passive"))
    )
    (net (code "114") (name "unconnected-(J3-Pad9)") (class "Default")
      (node (ref "J3") (pin "9") (pinfunction "9_9") (pintype "passive"))
    )
    (net (code "115") (name "unconnected-(J3-Pad10)") (class "Default")
      (node (ref "J3") (pin "10") (pinfunction "10_10") (pintype "passive"))
    )
    (net (code "116") (name "unconnected-(J3-Pad11)") (class "Default")
      (node (ref "J3") (pin "11") (pinfunction "11_11") (pintype "passive"))
    )
    (net (code "117") (name "unconnected-(J3-Pad12)") (class "Default")
      (node (ref "J3") (pin "12") (pinfunction "12_12") (pintype "passive"))
    )
    (net (code "118") (name "unconnected-(J4-Pad7)") (class "Default")
      (node (ref "J4") (pin "7") (pinfunction "7_7") (pintype "passive"))
    )
    (net (code "119") (name "unconnected-(J4-Pad8)") (class "Default")
      (node (ref "J4") (pin "8") (pinfunction "8_8") (pintype "passive"))
    )
    (net (code "120") (name "unconnected-(J4-Pad9)") (class "Default")
      (node (ref "J4") (pin "9") (pinfunction "9_9") (pintype "passive"))
    )
    (net (code "121") (name "unconnected-(J4-Pad10)") (class "Default")
      (node (ref "J4") (pin "10") (pinfunction "10_10") (pintype "passive"))
    )
    (net (code "122") (name "unconnected-(J4-Pad11)") (class "Default")
      (node (ref "J4") (pin "11") (pinfunction "11_11") (pintype "passive"))
    )
    (net (code "123") (name "unconnected-(J4-Pad12)") (class "Default")
      (node (ref "J4") (pin "12") (pinfunction "12_12") (pintype "passive"))
    )
    (net (code "124") (name "unconnected-(J5-Pad9)") (class "Default")
      (node (ref "J5") (pin "9") (pinfunction "9_9") (pintype "passive"))
    )
    (net (code "125") (name "unconnected-(J5-Pad10)") (class "Default")
      (node (ref "J5") (pin "10") (pinfunction "10_10") (pintype "passive"))
    )
    (net (code "126") (name "unconnected-(J5-Pad11)") (class "Default")
      (node (ref "J5") (pin "11") (pinfunction "11_11") (pintype "passive"))
    )
    (net (code "127") (name "unconnected-(J5-Pad12)") (class "Default")
      (node (ref "J5") (pin "12") (pinfunction "12_12") (pintype "passive"))
    )
    (net (code "128") (name "unconnected-(J6-Pad9)") (class "Default")
      (node (ref "J6") (pin "9") (pinfunction "9_9") (pintype "passive"))
    )
    (net (code "129") (name "unconnected-(J6-Pad10)") (class "Default")
      (node (ref "J6") (pin "10") (pinfunction "10_10") (pintype "passive"))
    )
    (net (code "130") (name "unconnected-(J6-Pad11)") (class "Default")
      (node (ref "J6") (pin "11") (pinfunction "11_11") (pintype "passive"))
    )
    (net (code "131") (name "unconnected-(J6-Pad12)") (class "Default")
      (node (ref "J6") (pin "12") (pinfunction "12_12") (pintype "passive"))
    )
    (net (code "132") (name "unconnected-(J7-Pad9)") (class "Default")
      (node (ref "J7") (pin "9") (pinfunction "9_9") (pintype "passive"))
    )
    (net (code "133") (name "unconnected-(J7-Pad10)") (class "Default")
      (node (ref "J7") (pin "10") (pinfunction "10_10") (pintype "passive"))
    )
    (net (code "134") (name "unconnected-(J7-Pad11)") (class "Default")
      (node (ref "J7") (pin "11") (pinfunction "11_11") (pintype "passive"))
    )
    (net (code "135") (name "unconnected-(J7-Pad12)") (class "Default")
      (node (ref "J7") (pin "12") (pinfunction "12_12") (pintype "passive"))
    )
    (net (code "136") (name "unconnected-(J8-Pad7)") (class "Default")
      (node (ref "J8") (pin "7") (pinfunction "7_7") (pintype "passive"))
    )
    (net (code "137") (name "unconnected-(J8-Pad8)") (class "Default")
      (node (ref "J8") (pin "8") (pinfunction "8_8") (pintype "passive"))
    )
    (net (code "138") (name "unconnected-(J8-Pad9)") (class "Default")
      (node (ref "J8") (pin "9") (pinfunction "9_9") (pintype "passive"))
    )
    (net (code "139") (name "unconnected-(J8-Pad10)") (class "Default")
      (node (ref "J8") (pin "10") (pinfunction "10_10") (pintype "passive"))
    )
    (net (code "140") (name "unconnected-(J8-Pad11)") (class "Default")
      (node (ref "J8") (pin "11") (pinfunction "11_11") (pintype "passive"))
    )
    (net (code "141") (name "unconnected-(J8-Pad12)") (class "Default")
      (node (ref "J8") (pin "12") (pinfunction "12_12") (pintype "passive"))
    )
    (net (code "142") (name "unconnected-(X1-1-Pad10)") (class "Default")
      (node (ref "X1-1") (pin "10") (pinfunction "10_10") (pintype "passive+no_connect"))
    )
    (net (code "143") (name "unconnected-(X1-2-Pad18)") (class "Default")
      (node (ref "X1-2") (pin "18") (pinfunction "18_18") (pintype "passive"))
    )
    (net (code "144") (name "unconnected-(X1-2-Pad19)") (class "Default")
      (node (ref "X1-2") (pin "19") (pinfunction "19_19") (pintype "passive"))
    )
    (net (code "145") (name "unconnected-(Z2-Pad77)") (class "Default")
      (node (ref "Z2") (pin "77") (pinfunction "77_77") (pintype "passive+no_connect"))
    )
    (net (code "146") (name "unconnected-(Z2-Pad78)") (class "Default")
      (node (ref "Z2") (pin "78") (pinfunction "78_78") (pintype "passive+no_connect"))
    )
    (net (code "147") (name "unconnected-(Z2-Pad79)") (class "Default")
      (node (ref "Z2") (pin "79") (pinfunction "79_79") (pintype "passive+no_connect"))
    )
    (net (code "148") (name "unconnected-(Z2-Pad80)") (class "Default")
      (node (ref "Z2") (pin "80") (pinfunction "80_80") (pintype "passive+no_connect"))
    )
    (net (code "149") (name "unconnected-(Z2-Pad81)") (class "Default")
      (node (ref "Z2") (pin "81") (pinfunction "81_81") (pintype "passive+no_connect"))
    )
    (net (code "150") (name "unconnected-(Z2-Pad82)") (class "Default")
      (node (ref "Z2") (pin "82") (pinfunction "82_82") (pintype "passive+no_connect"))
    )
    (net (code "151") (name "unconnected-(Z2-Pad83)") (class "Default")
      (node (ref "Z2") (pin "83") (pinfunction "83_83") (pintype "passive+no_connect"))
    )
    (net (code "152") (name "unconnected-(Z2-Pad84)") (class "Default")
      (node (ref "Z2") (pin "84") (pinfunction "84_84") (pintype "passive+no_connect"))
    )
    (net (code "153") (name "unconnected-(Z2-Pad85)") (class "Default")
      (node (ref "Z2") (pin "85") (pinfunction "85_85") (pintype "passive+no_connect"))
    )
    (net (code "154") (name "unconnected-(Z2-Pad86)") (class "Default")
      (node (ref "Z2") (pin "86") (pinfunction "86_86") (pintype "passive+no_connect"))
    )
  )
)
